# SCH_Bachelor-thesis_2025-02-08.net
KiCad netlist of a schematic drawn in EasyEDA
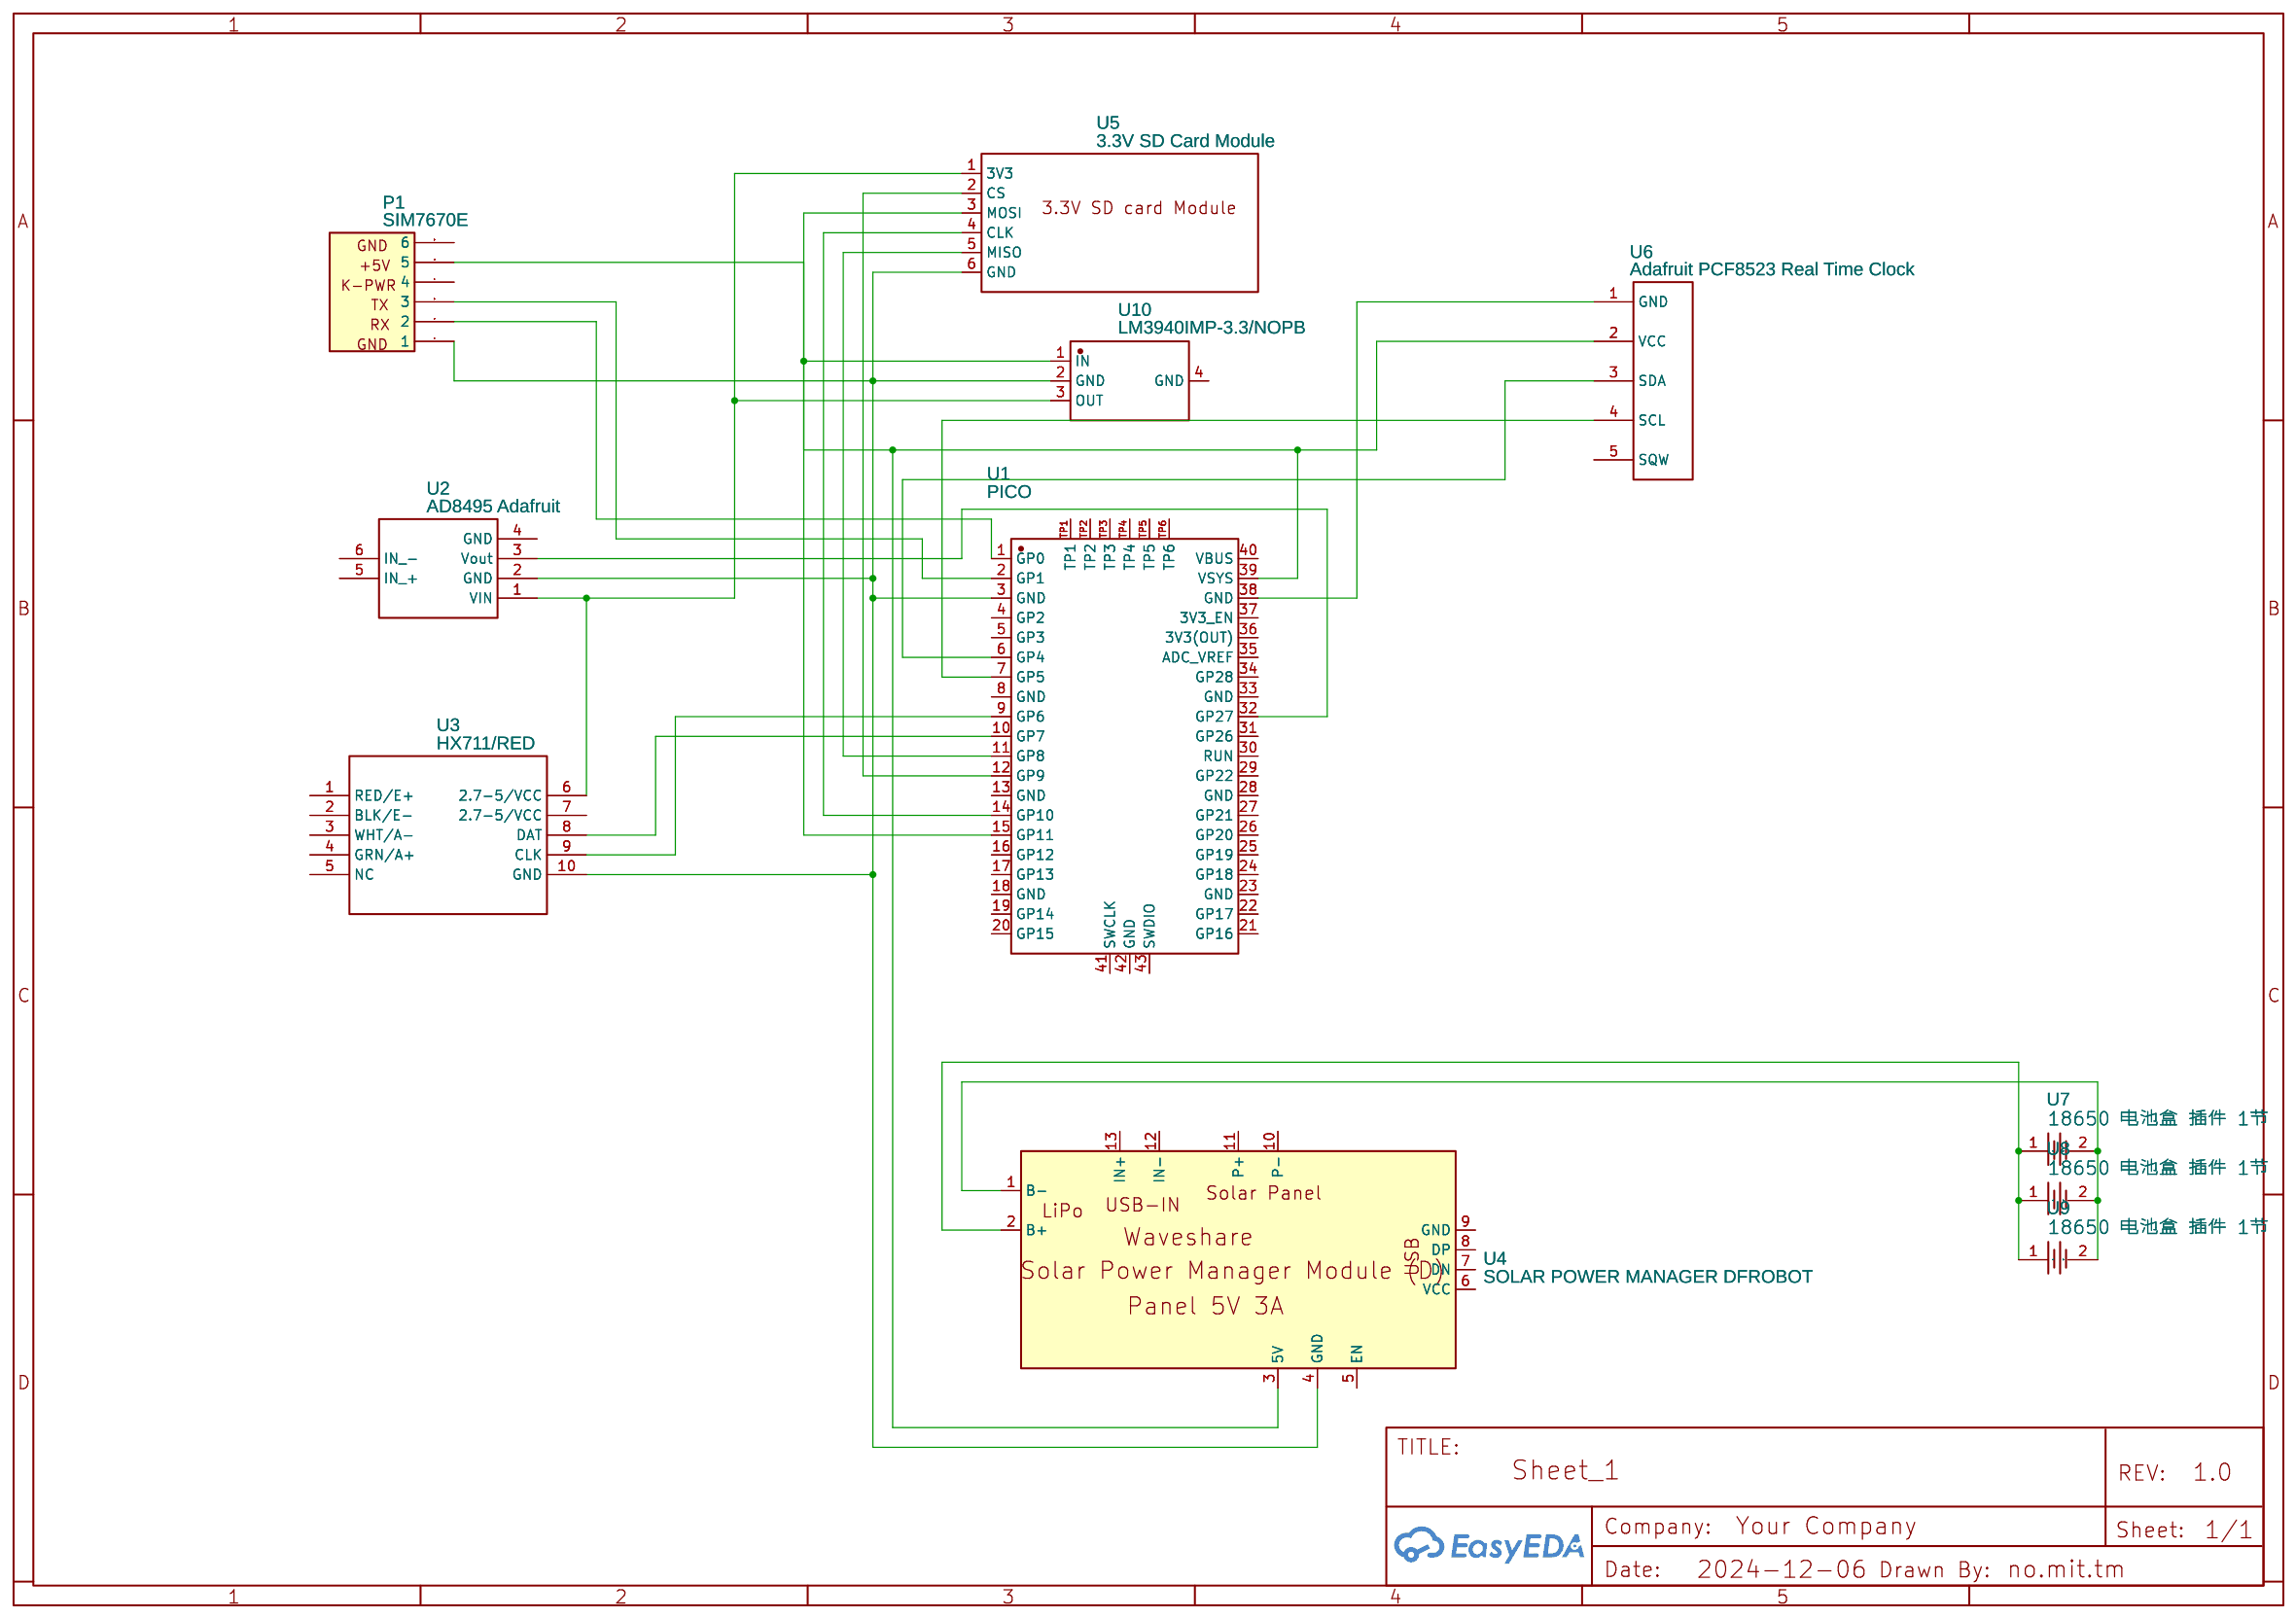
[diagram p0: schematic sheet]

(export (version "E")
  (design (tool "Eeschema 10.0.6"))
  (components
    (comp (ref "P1")
      (value "SIM7670E")
      (fields (field (name "Manufacturer Part") "Header-Male-2.54_1x6") (field (name "Manufacturer") "LCSC"))
      (libsource (lib "") (part "SIM7670E"))
    )
    (comp (ref "U1")
      (value "PICO")
      (fields (field (name "Manufacturer") "Raspberry Pi(树莓派)"))
      (libsource (lib "") (part "PICO"))
    )
    (comp (ref "U2")
      (value "AD8495 Adafruit")
      (fields (field (name "Manufacturer Part") "1778") (field (name "Manufacturer") "Adafruit"))
      (libsource (lib "") (part "AD8495 Adafruit"))
    )
    (comp (ref "U3") (value "HX711/RED") (libsource (lib "") (part "HX711/RED")))
    (comp (ref "U4")
      (value "SOLAR POWER MANAGER DFROBOT")
      (fields (field (name "Manufacturer Part") "Sunflower"))
      (libsource (lib "") (part "SOLAR POWER MANAGER DFROBOT"))
    )
    (comp (ref "U5") (value "3.3V SD Card Module") (libsource (lib "") (part "3.3V SD Card Module")))
    (comp (ref "U6")
      (value "Adafruit PCF8523 Real Time Clock")
      (libsource (lib "") (part "Adafruit PCF8523 Real Time Clock"))
    )
    (comp (ref "U7") (value "18650 电池盒 插件 1节") (libsource (lib "") (part "18650 电池盒 插件 1节")))
    (comp (ref "U8") (value "18650 电池盒 插件 1节") (libsource (lib "") (part "18650 电池盒 插件 1节")))
    (comp (ref "U9") (value "18650 电池盒 插件 1节") (libsource (lib "") (part "18650 电池盒 插件 1节")))
    (comp (ref "U10")
      (value "LM3940IMP-3.3/NOPB")
      (fields (field (name "Manufacturer") "TI(德州仪器)"))
      (libsource (lib "") (part "LM3940IMP-3.3/NOPB"))
    )
  )
  (nets
    (net (code "1") (name "Net-(U1-GP0)") (class "Default")
      (node (ref "P1") (pin "2") (pinfunction "2_2") (pintype "input"))
      (node (ref "U1") (pin "1") (pinfunction "GP0_1") (pintype "unspecified"))
    )
    (net (code "2") (name "Net-(U1-GP1)") (class "Default")
      (node (ref "P1") (pin "3") (pinfunction "3_3") (pintype "input"))
      (node (ref "U1") (pin "2") (pinfunction "GP1_2") (pintype "unspecified"))
    )
    (net (code "3") (name "Net-(U1-GP4)") (class "Default")
      (node (ref "U1") (pin "6") (pinfunction "GP4_6") (pintype "unspecified"))
      (node (ref "U6") (pin "3") (pinfunction "SDA_3") (pintype "unspecified"))
    )
    (net (code "4") (name "Net-(U1-GP5)") (class "Default")
      (node (ref "U1") (pin "7") (pinfunction "GP5_7") (pintype "unspecified"))
      (node (ref "U6") (pin "4") (pinfunction "SCL_4") (pintype "unspecified"))
    )
    (net (code "5") (name "Net-(U1-GP6)") (class "Default")
      (node (ref "U1") (pin "9") (pinfunction "GP6_9") (pintype "unspecified"))
      (node (ref "U3") (pin "9") (pinfunction "CLK_9") (pintype "unspecified"))
    )
    (net (code "6") (name "Net-(U1-GP7)") (class "Default")
      (node (ref "U1") (pin "10") (pinfunction "GP7_10") (pintype "unspecified"))
      (node (ref "U3") (pin "8") (pinfunction "DAT_8") (pintype "unspecified"))
    )
    (net (code "7") (name "Net-(U1-GP8)") (class "Default")
      (node (ref "U1") (pin "11") (pinfunction "GP8_11") (pintype "unspecified"))
      (node (ref "U5") (pin "5") (pinfunction "MISO_5") (pintype "input"))
    )
    (net (code "8") (name "Net-(U1-GP9)") (class "Default")
      (node (ref "U1") (pin "12") (pinfunction "GP9_12") (pintype "unspecified"))
      (node (ref "U5") (pin "2") (pinfunction "CS_2") (pintype "bidirectional"))
    )
    (net (code "9") (name "Net-(U1-GP10)") (class "Default")
      (node (ref "U1") (pin "14") (pinfunction "GP10_14") (pintype "unspecified"))
      (node (ref "U5") (pin "4") (pinfunction "CLK_4") (pintype "unspecified"))
    )
    (net (code "10") (name "Net-(U1-GP11)") (class "Default")
      (node (ref "P1") (pin "5") (pinfunction "5_5") (pintype "input"))
      (node (ref "U1") (pin "15") (pinfunction "GP11_15") (pintype "unspecified"))
      (node (ref "U1") (pin "39") (pinfunction "VSYS_39") (pintype "unspecified"))
      (node (ref "U10") (pin "1") (pinfunction "IN_1") (pintype "unspecified"))
      (node (ref "U4") (pin "3") (pinfunction "5V_3") (pintype "unspecified"))
      (node (ref "U5") (pin "3") (pinfunction "MOSI_3") (pintype "passive"))
      (node (ref "U6") (pin "2") (pinfunction "VCC_2") (pintype "unspecified"))
    )
    (net (code "11") (name "Net-(U1-GP27)") (class "Default")
      (node (ref "U1") (pin "32") (pinfunction "GP27_32") (pintype "unspecified"))
      (node (ref "U2") (pin "3") (pinfunction "Vout_3") (pintype "unspecified"))
    )
    (net (code "12") (name "Net-(U3-GND)") (class "Default")
      (node (ref "P1") (pin "1") (pinfunction "1_1") (pintype "input"))
      (node (ref "U1") (pin "3") (pinfunction "GND_3") (pintype "unspecified"))
      (node (ref "U10") (pin "2") (pinfunction "GND_2") (pintype "unspecified"))
      (node (ref "U2") (pin "2") (pinfunction "GND_2") (pintype "unspecified"))
      (node (ref "U3") (pin "10") (pinfunction "GND_10") (pintype "unspecified"))
      (node (ref "U4") (pin "4") (pinfunction "GND_4") (pintype "unspecified"))
      (node (ref "U5") (pin "6") (pinfunction "GND_6") (pintype "input"))
    )
    (net (code "13") (name "Net-(U4-B+)") (class "Default")
      (node (ref "U4") (pin "2") (pinfunction "B+_2") (pintype "unspecified"))
      (node (ref "U7") (pin "1") (pinfunction "1_1") (pintype "input"))
      (node (ref "U8") (pin "1") (pinfunction "1_1") (pintype "input"))
      (node (ref "U9") (pin "1") (pinfunction "1_1") (pintype "input"))
    )
    (net (code "14") (name "Net-(U4-B-)") (class "Default")
      (node (ref "U4") (pin "1") (pinfunction "B-_1") (pintype "unspecified"))
      (node (ref "U7") (pin "2") (pinfunction "2_2") (pintype "input"))
      (node (ref "U8") (pin "2") (pinfunction "2_2") (pintype "input"))
      (node (ref "U9") (pin "2") (pinfunction "2_2") (pintype "input"))
    )
    (net (code "15") (name "Net-(U6-GND)") (class "Default")
      (node (ref "U1") (pin "38") (pinfunction "GND_38") (pintype "unspecified"))
      (node (ref "U6") (pin "1") (pinfunction "GND_1") (pintype "unspecified"))
    )
    (net (code "16") (name "Net-(U10-OUT)") (class "Default")
      (node (ref "U10") (pin "3") (pinfunction "OUT_3") (pintype "unspecified"))
      (node (ref "U2") (pin "1") (pinfunction "VIN_1") (pintype "unspecified"))
      (node (ref "U3") (pin "6") (pinfunction "2.7-5/VCC_6") (pintype "unspecified"))
      (node (ref "U5") (pin "1") (pinfunction "3V3_1") (pintype "input"))
    )
    (net (code "17") (name "unconnected-(P1-Pad4)") (class "Default")
      (node (ref "P1") (pin "4") (pinfunction "4_4") (pintype "input"))
    )
    (net (code "18") (name "unconnected-(P1-Pad6)") (class "Default")
      (node (ref "P1") (pin "6") (pinfunction "6_6") (pintype "input"))
    )
    (net (code "19") (name "unconnected-(U1-3V3(OUT)-Pad36)") (class "Default")
      (node (ref "U1") (pin "36") (pinfunction "3V3(OUT)_36") (pintype "unspecified"))
    )
    (net (code "20") (name "unconnected-(U1-3V3_EN-Pad37)") (class "Default")
      (node (ref "U1") (pin "37") (pinfunction "3V3_EN_37") (pintype "unspecified"))
    )
    (net (code "21") (name "unconnected-(U1-ADC_VREF-Pad35)") (class "Default")
      (node (ref "U1") (pin "35") (pinfunction "ADC_VREF_35") (pintype "unspecified"))
    )
    (net (code "22") (name "unconnected-(U1-GND-Pad8)") (class "Default")
      (node (ref "U1") (pin "8") (pinfunction "GND_8") (pintype "unspecified"))
    )
    (net (code "23") (name "unconnected-(U1-GND-Pad13)") (class "Default")
      (node (ref "U1") (pin "13") (pinfunction "GND_13") (pintype "unspecified"))
    )
    (net (code "24") (name "unconnected-(U1-GND-Pad18)") (class "Default")
      (node (ref "U1") (pin "18") (pinfunction "GND_18") (pintype "unspecified"))
    )
    (net (code "25") (name "unconnected-(U1-GND-Pad23)") (class "Default")
      (node (ref "U1") (pin "23") (pinfunction "GND_23") (pintype "unspecified"))
    )
    (net (code "26") (name "unconnected-(U1-GND-Pad28)") (class "Default")
      (node (ref "U1") (pin "28") (pinfunction "GND_28") (pintype "unspecified"))
    )
    (net (code "27") (name "unconnected-(U1-GND-Pad33)") (class "Default")
      (node (ref "U1") (pin "33") (pinfunction "GND_33") (pintype "unspecified"))
    )
    (net (code "28") (name "unconnected-(U1-GND-Pad42)") (class "Default")
      (node (ref "U1") (pin "42") (pinfunction "GND_42") (pintype "unspecified"))
    )
    (net (code "29") (name "unconnected-(U1-GP2-Pad4)") (class "Default")
      (node (ref "U1") (pin "4") (pinfunction "GP2_4") (pintype "unspecified"))
    )
    (net (code "30") (name "unconnected-(U1-GP3-Pad5)") (class "Default")
      (node (ref "U1") (pin "5") (pinfunction "GP3_5") (pintype "unspecified"))
    )
    (net (code "31") (name "unconnected-(U1-GP12-Pad16)") (class "Default")
      (node (ref "U1") (pin "16") (pinfunction "GP12_16") (pintype "unspecified"))
    )
    (net (code "32") (name "unconnected-(U1-GP13-Pad17)") (class "Default")
      (node (ref "U1") (pin "17") (pinfunction "GP13_17") (pintype "unspecified"))
    )
    (net (code "33") (name "unconnected-(U1-GP14-Pad19)") (class "Default")
      (node (ref "U1") (pin "19") (pinfunction "GP14_19") (pintype "unspecified"))
    )
    (net (code "34") (name "unconnected-(U1-GP15-Pad20)") (class "Default")
      (node (ref "U1") (pin "20") (pinfunction "GP15_20") (pintype "unspecified"))
    )
    (net (code "35") (name "unconnected-(U1-GP16-Pad21)") (class "Default")
      (node (ref "U1") (pin "21") (pinfunction "GP16_21") (pintype "unspecified"))
    )
    (net (code "36") (name "unconnected-(U1-GP17-Pad22)") (class "Default")
      (node (ref "U1") (pin "22") (pinfunction "GP17_22") (pintype "unspecified"))
    )
    (net (code "37") (name "unconnected-(U1-GP18-Pad24)") (class "Default")
      (node (ref "U1") (pin "24") (pinfunction "GP18_24") (pintype "unspecified"))
    )
    (net (code "38") (name "unconnected-(U1-GP19-Pad25)") (class "Default")
      (node (ref "U1") (pin "25") (pinfunction "GP19_25") (pintype "unspecified"))
    )
    (net (code "39") (name "unconnected-(U1-GP20-Pad26)") (class "Default")
      (node (ref "U1") (pin "26") (pinfunction "GP20_26") (pintype "unspecified"))
    )
    (net (code "40") (name "unconnected-(U1-GP21-Pad27)") (class "Default")
      (node (ref "U1") (pin "27") (pinfunction "GP21_27") (pintype "unspecified"))
    )
    (net (code "41") (name "unconnected-(U1-GP22-Pad29)") (class "Default")
      (node (ref "U1") (pin "29") (pinfunction "GP22_29") (pintype "unspecified"))
    )
    (net (code "42") (name "unconnected-(U1-GP26-Pad31)") (class "Default")
      (node (ref "U1") (pin "31") (pinfunction "GP26_31") (pintype "unspecified"))
    )
    (net (code "43") (name "unconnected-(U1-GP28-Pad34)") (class "Default")
      (node (ref "U1") (pin "34") (pinfunction "GP28_34") (pintype "unspecified"))
    )
    (net (code "44") (name "unconnected-(U1-PadTP1)") (class "Default")
      (node (ref "U1") (pin "TP1") (pinfunction "TP1_TP1") (pintype "unspecified"))
    )
    (net (code "45") (name "unconnected-(U1-PadTP2)") (class "Default")
      (node (ref "U1") (pin "TP2") (pinfunction "TP2_TP2") (pintype "unspecified"))
    )
    (net (code "46") (name "unconnected-(U1-PadTP3)") (class "Default")
      (node (ref "U1") (pin "TP3") (pinfunction "TP3_TP3") (pintype "unspecified"))
    )
    (net (code "47") (name "unconnected-(U1-PadTP4)") (class "Default")
      (node (ref "U1") (pin "TP4") (pinfunction "TP4_TP4") (pintype "unspecified"))
    )
    (net (code "48") (name "unconnected-(U1-PadTP5)") (class "Default")
      (node (ref "U1") (pin "TP5") (pinfunction "TP5_TP5") (pintype "unspecified"))
    )
    (net (code "49") (name "unconnected-(U1-PadTP6)") (class "Default")
      (node (ref "U1") (pin "TP6") (pinfunction "TP6_TP6") (pintype "unspecified"))
    )
    (net (code "50") (name "unconnected-(U1-RUN-Pad30)") (class "Default")
      (node (ref "U1") (pin "30") (pinfunction "RUN_30") (pintype "unspecified"))
    )
    (net (code "51") (name "unconnected-(U1-SWCLK-Pad41)") (class "Default")
      (node (ref "U1") (pin "41") (pinfunction "SWCLK_41") (pintype "unspecified"))
    )
    (net (code "52") (name "unconnected-(U1-SWDIO-Pad43)") (class "Default")
      (node (ref "U1") (pin "43") (pinfunction "SWDIO_43") (pintype "unspecified"))
    )
    (net (code "53") (name "unconnected-(U1-VBUS-Pad40)") (class "Default")
      (node (ref "U1") (pin "40") (pinfunction "VBUS_40") (pintype "unspecified"))
    )
    (net (code "54") (name "unconnected-(U2-GND-Pad4)") (class "Default")
      (node (ref "U2") (pin "4") (pinfunction "GND_4") (pintype "unspecified"))
    )
    (net (code "55") (name "unconnected-(U2-IN_+-Pad5)") (class "Default")
      (node (ref "U2") (pin "5") (pinfunction "IN_+_5") (pintype "unspecified"))
    )
    (net (code "56") (name "unconnected-(U2-IN_--Pad6)") (class "Default")
      (node (ref "U2") (pin "6") (pinfunction "IN_-_6") (pintype "unspecified"))
    )
    (net (code "57") (name "unconnected-(U3-2.7-5{slash}VCC-Pad7)") (class "Default")
      (node (ref "U3") (pin "7") (pinfunction "2.7-5/VCC_7") (pintype "unspecified"))
    )
    (net (code "58") (name "unconnected-(U3-BLK{slash}E--Pad2)") (class "Default")
      (node (ref "U3") (pin "2") (pinfunction "BLK/E-_2") (pintype "unspecified"))
    )
    (net (code "59") (name "unconnected-(U3-GRN{slash}A+-Pad4)") (class "Default")
      (node (ref "U3") (pin "4") (pinfunction "GRN/A+_4") (pintype "unspecified"))
    )
    (net (code "60") (name "unconnected-(U3-NC-Pad5)") (class "Default")
      (node (ref "U3") (pin "5") (pinfunction "NC_5") (pintype "unspecified"))
    )
    (net (code "61") (name "unconnected-(U3-RED{slash}E+-Pad1)") (class "Default")
      (node (ref "U3") (pin "1") (pinfunction "RED/E+_1") (pintype "unspecified"))
    )
    (net (code "62") (name "unconnected-(U3-WHT{slash}A--Pad3)") (class "Default")
      (node (ref "U3") (pin "3") (pinfunction "WHT/A-_3") (pintype "unspecified"))
    )
    (net (code "63") (name "unconnected-(U4-DN-Pad7)") (class "Default")
      (node (ref "U4") (pin "7") (pinfunction "DN_7") (pintype "unspecified"))
    )
    (net (code "64") (name "unconnected-(U4-DP-Pad8)") (class "Default")
      (node (ref "U4") (pin "8") (pinfunction "DP_8") (pintype "unspecified"))
    )
    (net (code "65") (name "unconnected-(U4-EN-Pad5)") (class "Default")
      (node (ref "U4") (pin "5") (pinfunction "EN_5") (pintype "unspecified"))
    )
    (net (code "66") (name "unconnected-(U4-GND-Pad9)") (class "Default")
      (node (ref "U4") (pin "9") (pinfunction "GND_9") (pintype "unspecified"))
    )
    (net (code "67") (name "unconnected-(U4-IN+-Pad13)") (class "Default")
      (node (ref "U4") (pin "13") (pinfunction "IN+_13") (pintype "unspecified"))
    )
    (net (code "68") (name "unconnected-(U4-IN--Pad12)") (class "Default")
      (node (ref "U4") (pin "12") (pinfunction "IN-_12") (pintype "unspecified"))
    )
    (net (code "69") (name "unconnected-(U4-P+-Pad11)") (class "Default")
      (node (ref "U4") (pin "11") (pinfunction "P+_11") (pintype "unspecified"))
    )
    (net (code "70") (name "unconnected-(U4-P--Pad10)") (class "Default")
      (node (ref "U4") (pin "10") (pinfunction "P-_10") (pintype "unspecified"))
    )
    (net (code "71") (name "unconnected-(U4-VCC-Pad6)") (class "Default")
      (node (ref "U4") (pin "6") (pinfunction "VCC_6") (pintype "unspecified"))
    )
    (net (code "72") (name "unconnected-(U6-SQW-Pad5)") (class "Default")
      (node (ref "U6") (pin "5") (pinfunction "SQW_5") (pintype "unspecified"))
    )
    (net (code "73") (name "unconnected-(U10-GND-Pad4)") (class "Default")
      (node (ref "U10") (pin "4") (pinfunction "GND_4") (pintype "unspecified"))
    )
  )
)
